# LEAF2GRID.net
KiCad netlist of a schematic drawn in Altium Designer
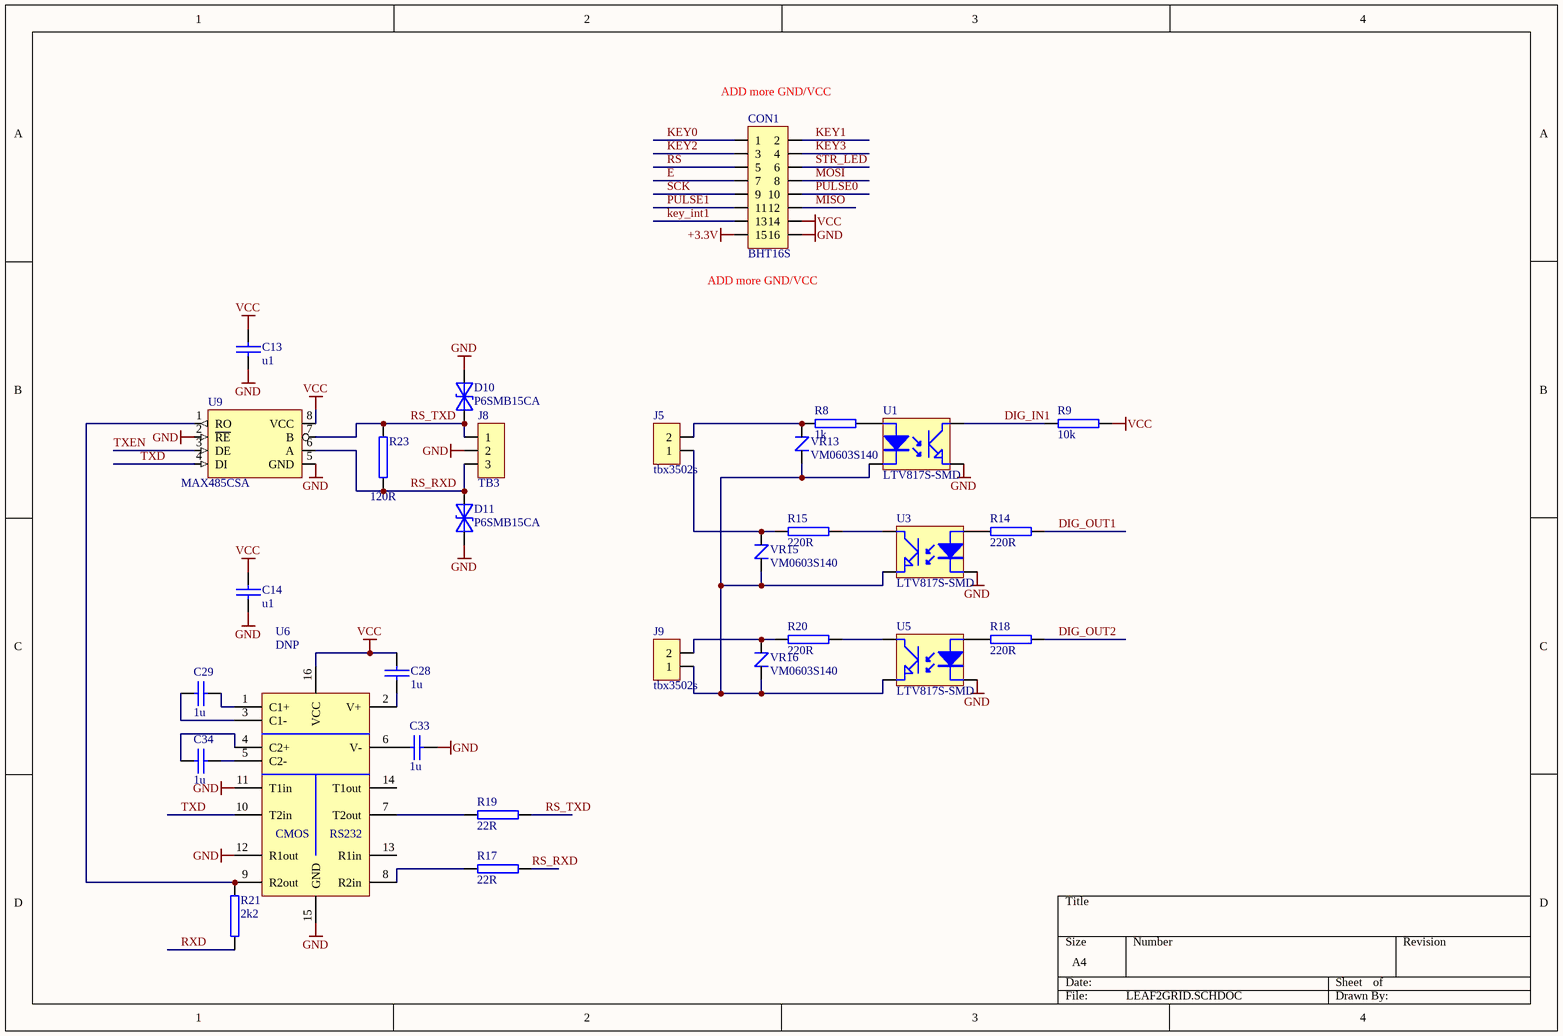
[diagram p0: LEAF2GRID.SCHDOC]

(export (version "E")
  (design (tool "Eeschema 10.0.6"))
  (components
    (comp (ref "C13")
      (value "u1")
      (footprint "0603")
      (description "Capacitor SMD")
      (libsource (lib "LIBRARY_SCH") (part "CAP_SMD"))
    )
    (comp (ref "C14")
      (value "u1")
      (footprint "0603")
      (description "Capacitor SMD")
      (libsource (lib "LIBRARY_SCH") (part "CAP_SMD"))
    )
    (comp (ref "C28")
      (value "1u")
      (footprint "0805")
      (description "Capacitor")
      (libsource (lib "LIBRARY_SCH") (part "CAP"))
    )
    (comp (ref "C29")
      (value "1u")
      (footprint "0805")
      (description "Capacitor")
      (libsource (lib "LIBRARY_SCH") (part "CAP"))
    )
    (comp (ref "C33")
      (value "1u")
      (footprint "0805")
      (description "Capacitor")
      (libsource (lib "LIBRARY_SCH") (part "CAP"))
    )
    (comp (ref "C34")
      (value "1u")
      (footprint "0805")
      (description "Capacitor")
      (libsource (lib "LIBRARY_SCH") (part "CAP"))
    )
    (comp (ref "CON1")
      (value "BHT16S")
      (footprint "BHT16S")
      (description "Maritex BH16S")
      (libsource (lib "LIBRARY_SCH") (part "CON_IDC16_SMT"))
    )
    (comp (ref "D10")
      (value "P6SMB15CA")
      (footprint "DO-214AA/SMB")
      (description "transil 600W")
      (libsource (lib "LIBRARY_SCH") (part "TRANSIL 1.5KE"))
    )
    (comp (ref "D11")
      (value "P6SMB15CA")
      (footprint "DO-214AA/SMB")
      (description "transil 600W")
      (libsource (lib "LIBRARY_SCH") (part "TRANSIL 1.5KE"))
    )
    (comp (ref "J5")
      (value "tbx3502s")
      (footprint "tbx3502s")
      (description "Terminal Block")
      (libsource (lib "LIBRARY_SCH") (part "TB2"))
    )
    (comp (ref "J8")
      (value "TB3")
      (footprint "tbx3503s")
      (description "Terminal Block")
      (libsource (lib "LIBRARY_SCH") (part "TB3"))
    )
    (comp (ref "J9")
      (value "tbx3502s")
      (footprint "tbx3502s")
      (description "Terminal Block")
      (libsource (lib "LIBRARY_SCH") (part "TB2"))
    )
    (comp (ref "R8")
      (value "1k")
      (footprint "0603")
      (description "SMD Resistor")
      (libsource (lib "LIBRARY_SCH") (part "RES_SMD"))
    )
    (comp (ref "R9")
      (value "10k")
      (footprint "0603")
      (description "SMD Resistor")
      (libsource (lib "LIBRARY_SCH") (part "RES_SMD"))
    )
    (comp (ref "R14")
      (value "220R")
      (footprint "0603")
      (description "SMD Resistor")
      (libsource (lib "LIBRARY_SCH") (part "RES_SMD"))
    )
    (comp (ref "R15")
      (value "220R")
      (footprint "0603")
      (description "SMD Resistor")
      (libsource (lib "LIBRARY_SCH") (part "RES_SMD"))
    )
    (comp (ref "R17")
      (value "22R")
      (footprint "0603")
      (description "SMD Resistor")
      (libsource (lib "LIBRARY_SCH") (part "RES_SMD"))
    )
    (comp (ref "R18")
      (value "220R")
      (footprint "0603")
      (description "SMD Resistor")
      (libsource (lib "LIBRARY_SCH") (part "RES_SMD"))
    )
    (comp (ref "R19")
      (value "22R")
      (footprint "0603")
      (description "SMD Resistor")
      (libsource (lib "LIBRARY_SCH") (part "RES_SMD"))
    )
    (comp (ref "R20")
      (value "220R")
      (footprint "0603")
      (description "SMD Resistor")
      (libsource (lib "LIBRARY_SCH") (part "RES_SMD"))
    )
    (comp (ref "R21")
      (value "2k2")
      (footprint "0603")
      (description "SMD Resistor")
      (libsource (lib "LIBRARY_SCH") (part "RES_SMD"))
    )
    (comp (ref "R23")
      (value "120R")
      (footprint "1206")
      (description "SMD Resistor")
      (libsource (lib "LIBRARY_SCH") (part "RES_SMD"))
    )
    (comp (ref "U1")
      (value "LTV817S-SMD")
      (footprint "SOP_4")
      (description "transoptor")
      (libsource (lib "") (part "OPTO-LTV817S_1"))
    )
    (comp (ref "U3")
      (value "LTV817S-SMD")
      (footprint "SOP_4")
      (description "transoptor")
      (libsource (lib "LIBRARY_SCH") (part "OPTO-LTV817S"))
    )
    (comp (ref "U5")
      (value "LTV817S-SMD")
      (footprint "SOP_4")
      (description "transoptor")
      (libsource (lib "LIBRARY_SCH") (part "OPTO-LTV817S"))
    )
    (comp (ref "U6")
      (value "DNP")
      (footprint "so-16")
      (description "RS232 transceiver (Maritex)")
      (libsource (lib "LIBRARY_SCH") (part "MAX202"))
    )
    (comp (ref "U9") (value "MAX485CSA") (footprint "SO-8") (libsource (lib "*") (part "MAX485")))
    (comp (ref "VR13")
      (value "VM0603S140")
      (footprint "0603")
      (description "varistor SMD(Maritex)")
      (libsource (lib "LIBRARY_SCH") (part "Varistor VM0805Sxx"))
    )
    (comp (ref "VR15")
      (value "VM0603S140")
      (footprint "0603")
      (description "varistor SMD(Maritex)")
      (libsource (lib "LIBRARY_SCH") (part "Varistor VM0805Sxx"))
    )
    (comp (ref "VR16")
      (value "VM0603S140")
      (footprint "0603")
      (description "varistor SMD(Maritex)")
      (libsource (lib "LIBRARY_SCH") (part "Varistor VM0805Sxx"))
    )
  )
  (nets
    (net (code "1") (name "+3.3V") (class "Default")
      (node (ref "CON1") (pin "15") (pinfunction "15_15") (pintype "passive"))
    )
    (net (code "2") (name "/DIG_IN1") (class "Default")
      (node (ref "R9") (pin "2") (pinfunction "2_2") (pintype "passive"))
      (node (ref "U1") (pin "3") (pinfunction "C_3") (pintype "passive"))
    )
    (net (code "3") (name "/DIG_OUT1") (class "Default")
      (node (ref "R14") (pin "2") (pinfunction "2_2") (pintype "passive"))
    )
    (net (code "4") (name "/DIG_OUT2") (class "Default")
      (node (ref "R18") (pin "2") (pinfunction "2_2") (pintype "passive"))
    )
    (net (code "5") (name "/E") (class "Default")
      (node (ref "CON1") (pin "7") (pinfunction "7_7") (pintype "passive"))
    )
    (net (code "6") (name "/KEY0") (class "Default")
      (node (ref "CON1") (pin "1") (pinfunction "1_1") (pintype "passive"))
    )
    (net (code "7") (name "/KEY1") (class "Default")
      (node (ref "CON1") (pin "2") (pinfunction "2_2") (pintype "passive"))
    )
    (net (code "8") (name "/KEY2") (class "Default")
      (node (ref "CON1") (pin "3") (pinfunction "3_3") (pintype "passive"))
    )
    (net (code "9") (name "/KEY3") (class "Default")
      (node (ref "CON1") (pin "4") (pinfunction "4_4") (pintype "passive"))
    )
    (net (code "10") (name "/MISO") (class "Default")
      (node (ref "CON1") (pin "12") (pinfunction "12_12") (pintype "passive"))
    )
    (net (code "11") (name "/MOSI") (class "Default")
      (node (ref "CON1") (pin "8") (pinfunction "8_8") (pintype "passive"))
    )
    (net (code "12") (name "/PULSE0") (class "Default")
      (node (ref "CON1") (pin "10") (pinfunction "10_10") (pintype "passive"))
    )
    (net (code "13") (name "/PULSE1") (class "Default")
      (node (ref "CON1") (pin "11") (pinfunction "11_11") (pintype "passive"))
    )
    (net (code "14") (name "/RS") (class "Default")
      (node (ref "CON1") (pin "5") (pinfunction "5_5") (pintype "passive"))
    )
    (net (code "15") (name "/RS_RXD") (class "Default")
      (node (ref "D11") (pin "K") (pinfunction "K_K") (pintype "power_in"))
      (node (ref "J8") (pin "3") (pinfunction "3_3") (pintype "passive"))
      (node (ref "R17") (pin "2") (pinfunction "2_2") (pintype "passive"))
      (node (ref "R23") (pin "1") (pinfunction "1_1") (pintype "passive"))
      (node (ref "U9") (pin "6") (pinfunction "A_6") (pintype "bidirectional"))
    )
    (net (code "16") (name "/RS_TXD") (class "Default")
      (node (ref "D10") (pin "A") (pinfunction "A_A") (pintype "power_in"))
      (node (ref "J8") (pin "1") (pinfunction "1_1") (pintype "passive"))
      (node (ref "R19") (pin "2") (pinfunction "2_2") (pintype "passive"))
      (node (ref "R23") (pin "2") (pinfunction "2_2") (pintype "passive"))
      (node (ref "U9") (pin "7") (pinfunction "B_7") (pintype "bidirectional"))
    )
    (net (code "17") (name "/RXD") (class "Default")
      (node (ref "R21") (pin "1") (pinfunction "1_1") (pintype "passive"))
    )
    (net (code "18") (name "/SCK") (class "Default")
      (node (ref "CON1") (pin "9") (pinfunction "9_9") (pintype "passive"))
    )
    (net (code "19") (name "/STR_LED") (class "Default")
      (node (ref "CON1") (pin "6") (pinfunction "6_6") (pintype "passive"))
    )
    (net (code "20") (name "/TXD") (class "Default")
      (node (ref "U6") (pin "10") (pinfunction "T2in_10") (pintype "passive"))
      (node (ref "U9") (pin "4") (pinfunction "DI_4") (pintype "input"))
    )
    (net (code "21") (name "/TXEN") (class "Default")
      (node (ref "U9") (pin "3") (pinfunction "DE_3") (pintype "input"))
    )
    (net (code "22") (name "/key_int1") (class "Default")
      (node (ref "CON1") (pin "13") (pinfunction "13_13") (pintype "passive"))
    )
    (net (code "23") (name "GND") (class "Default")
      (node (ref "C13") (pin "1") (pinfunction "1_1") (pintype "passive"))
      (node (ref "C14") (pin "1") (pinfunction "1_1") (pintype "passive"))
      (node (ref "C33") (pin "2") (pinfunction "2_2") (pintype "passive"))
      (node (ref "CON1") (pin "16") (pinfunction "16_16") (pintype "passive"))
      (node (ref "D10") (pin "K") (pinfunction "K_K") (pintype "power_in"))
      (node (ref "D11") (pin "A") (pinfunction "A_A") (pintype "power_in"))
      (node (ref "J8") (pin "2") (pinfunction "2_2") (pintype "passive"))
      (node (ref "U1") (pin "4") (pinfunction "E_4") (pintype "passive"))
      (node (ref "U3") (pin "2") (pinfunction "K_2") (pintype "passive"))
      (node (ref "U5") (pin "2") (pinfunction "K_2") (pintype "passive"))
      (node (ref "U6") (pin "11") (pinfunction "T1in_11") (pintype "passive"))
      (node (ref "U6") (pin "12") (pinfunction "R1out_12") (pintype "passive"))
      (node (ref "U6") (pin "15") (pinfunction "GND_15") (pintype "passive"))
      (node (ref "U9") (pin "2") (pinfunction "~{RE}_2") (pintype "input"))
      (node (ref "U9") (pin "5") (pinfunction "GND_5") (pintype "power_in"))
    )
    (net (code "24") (name "Net-(J5-Pad1)") (class "Default")
      (node (ref "J5") (pin "1") (pinfunction "1_1") (pintype "passive"))
      (node (ref "R15") (pin "1") (pinfunction "1_1") (pintype "passive"))
      (node (ref "VR15") (pin "1") (pinfunction "1_1") (pintype "power_in"))
    )
    (net (code "25") (name "Net-(J5-Pad2)") (class "Default")
      (node (ref "J5") (pin "2") (pinfunction "2_2") (pintype "passive"))
      (node (ref "R8") (pin "1") (pinfunction "1_1") (pintype "passive"))
      (node (ref "VR13") (pin "1") (pinfunction "1_1") (pintype "power_in"))
    )
    (net (code "26") (name "Net-(J9-Pad2)") (class "Default")
      (node (ref "J9") (pin "2") (pinfunction "2_2") (pintype "passive"))
      (node (ref "R20") (pin "1") (pinfunction "1_1") (pintype "passive"))
      (node (ref "VR16") (pin "1") (pinfunction "1_1") (pintype "power_in"))
    )
    (net (code "27") (name "Net-(U1-A)") (class "Default")
      (node (ref "R8") (pin "2") (pinfunction "2_2") (pintype "passive"))
      (node (ref "U1") (pin "1") (pinfunction "A_1") (pintype "passive"))
    )
    (net (code "28") (name "Net-(U1-K)") (class "Default")
      (node (ref "J9") (pin "1") (pinfunction "1_1") (pintype "passive"))
      (node (ref "U1") (pin "2") (pinfunction "K_2") (pintype "passive"))
      (node (ref "U3") (pin "4") (pinfunction "E_4") (pintype "passive"))
      (node (ref "U5") (pin "4") (pinfunction "E_4") (pintype "passive"))
      (node (ref "VR13") (pin "2") (pinfunction "2_2") (pintype "power_in"))
      (node (ref "VR15") (pin "2") (pinfunction "2_2") (pintype "power_in"))
      (node (ref "VR16") (pin "2") (pinfunction "2_2") (pintype "power_in"))
    )
    (net (code "29") (name "Net-(U3-A)") (class "Default")
      (node (ref "R14") (pin "1") (pinfunction "1_1") (pintype "passive"))
      (node (ref "U3") (pin "1") (pinfunction "A_1") (pintype "passive"))
    )
    (net (code "30") (name "Net-(U3-C)") (class "Default")
      (node (ref "R15") (pin "2") (pinfunction "2_2") (pintype "passive"))
      (node (ref "U3") (pin "3") (pinfunction "C_3") (pintype "passive"))
    )
    (net (code "31") (name "Net-(U5-A)") (class "Default")
      (node (ref "R18") (pin "1") (pinfunction "1_1") (pintype "passive"))
      (node (ref "U5") (pin "1") (pinfunction "A_1") (pintype "passive"))
    )
    (net (code "32") (name "Net-(U5-C)") (class "Default")
      (node (ref "R20") (pin "2") (pinfunction "2_2") (pintype "passive"))
      (node (ref "U5") (pin "3") (pinfunction "C_3") (pintype "passive"))
    )
    (net (code "33") (name "Net-(U6-C1+)") (class "Default")
      (node (ref "C29") (pin "2") (pinfunction "2_2") (pintype "passive"))
      (node (ref "U6") (pin "1") (pinfunction "C1+_1") (pintype "passive"))
    )
    (net (code "34") (name "Net-(U6-C1-)") (class "Default")
      (node (ref "C29") (pin "1") (pinfunction "1_1") (pintype "passive"))
      (node (ref "U6") (pin "3") (pinfunction "C1-_3") (pintype "passive"))
    )
    (net (code "35") (name "Net-(U6-C2+)") (class "Default")
      (node (ref "C34") (pin "1") (pinfunction "1_1") (pintype "passive"))
      (node (ref "U6") (pin "4") (pinfunction "C2+_4") (pintype "passive"))
    )
    (net (code "36") (name "Net-(U6-C2-)") (class "Default")
      (node (ref "C34") (pin "2") (pinfunction "2_2") (pintype "passive"))
      (node (ref "U6") (pin "5") (pinfunction "C2-_5") (pintype "passive"))
    )
    (net (code "37") (name "Net-(U6-R2in)") (class "Default")
      (node (ref "R17") (pin "1") (pinfunction "1_1") (pintype "passive"))
      (node (ref "U6") (pin "8") (pinfunction "R2in_8") (pintype "passive"))
    )
    (net (code "38") (name "Net-(U6-R2out)") (class "Default")
      (node (ref "R21") (pin "2") (pinfunction "2_2") (pintype "passive"))
      (node (ref "U6") (pin "9") (pinfunction "R2out_9") (pintype "passive"))
      (node (ref "U9") (pin "1") (pinfunction "RO_1") (pintype "output"))
    )
    (net (code "39") (name "Net-(U6-T2out)") (class "Default")
      (node (ref "R19") (pin "1") (pinfunction "1_1") (pintype "passive"))
      (node (ref "U6") (pin "7") (pinfunction "T2out_7") (pintype "passive"))
    )
    (net (code "40") (name "Net-(U6-V+)") (class "Default")
      (node (ref "C28") (pin "1") (pinfunction "1_1") (pintype "passive"))
      (node (ref "U6") (pin "2") (pinfunction "V+_2") (pintype "passive"))
    )
    (net (code "41") (name "Net-(U6-V-)") (class "Default")
      (node (ref "C33") (pin "1") (pinfunction "1_1") (pintype "passive"))
      (node (ref "U6") (pin "6") (pinfunction "V-_6") (pintype "passive"))
    )
    (net (code "42") (name "VCC") (class "Default")
      (node (ref "C13") (pin "2") (pinfunction "2_2") (pintype "passive"))
      (node (ref "C14") (pin "2") (pinfunction "2_2") (pintype "passive"))
      (node (ref "C28") (pin "2") (pinfunction "2_2") (pintype "passive"))
      (node (ref "CON1") (pin "14") (pinfunction "14_14") (pintype "passive"))
      (node (ref "R9") (pin "1") (pinfunction "1_1") (pintype "passive"))
      (node (ref "U6") (pin "16") (pinfunction "VCC_16") (pintype "passive"))
      (node (ref "U9") (pin "8") (pinfunction "VCC_8") (pintype "power_in"))
    )
    (net (code "43") (name "unconnected-(U6-R1in-Pad13)") (class "Default")
      (node (ref "U6") (pin "13") (pinfunction "R1in_13") (pintype "passive"))
    )
    (net (code "44") (name "unconnected-(U6-T1out-Pad14)") (class "Default")
      (node (ref "U6") (pin "14") (pinfunction "T1out_14") (pintype "passive"))
    )
  )
)
